# RAMPS2.net
KiCad netlist of a schematic drawn in EAGLE
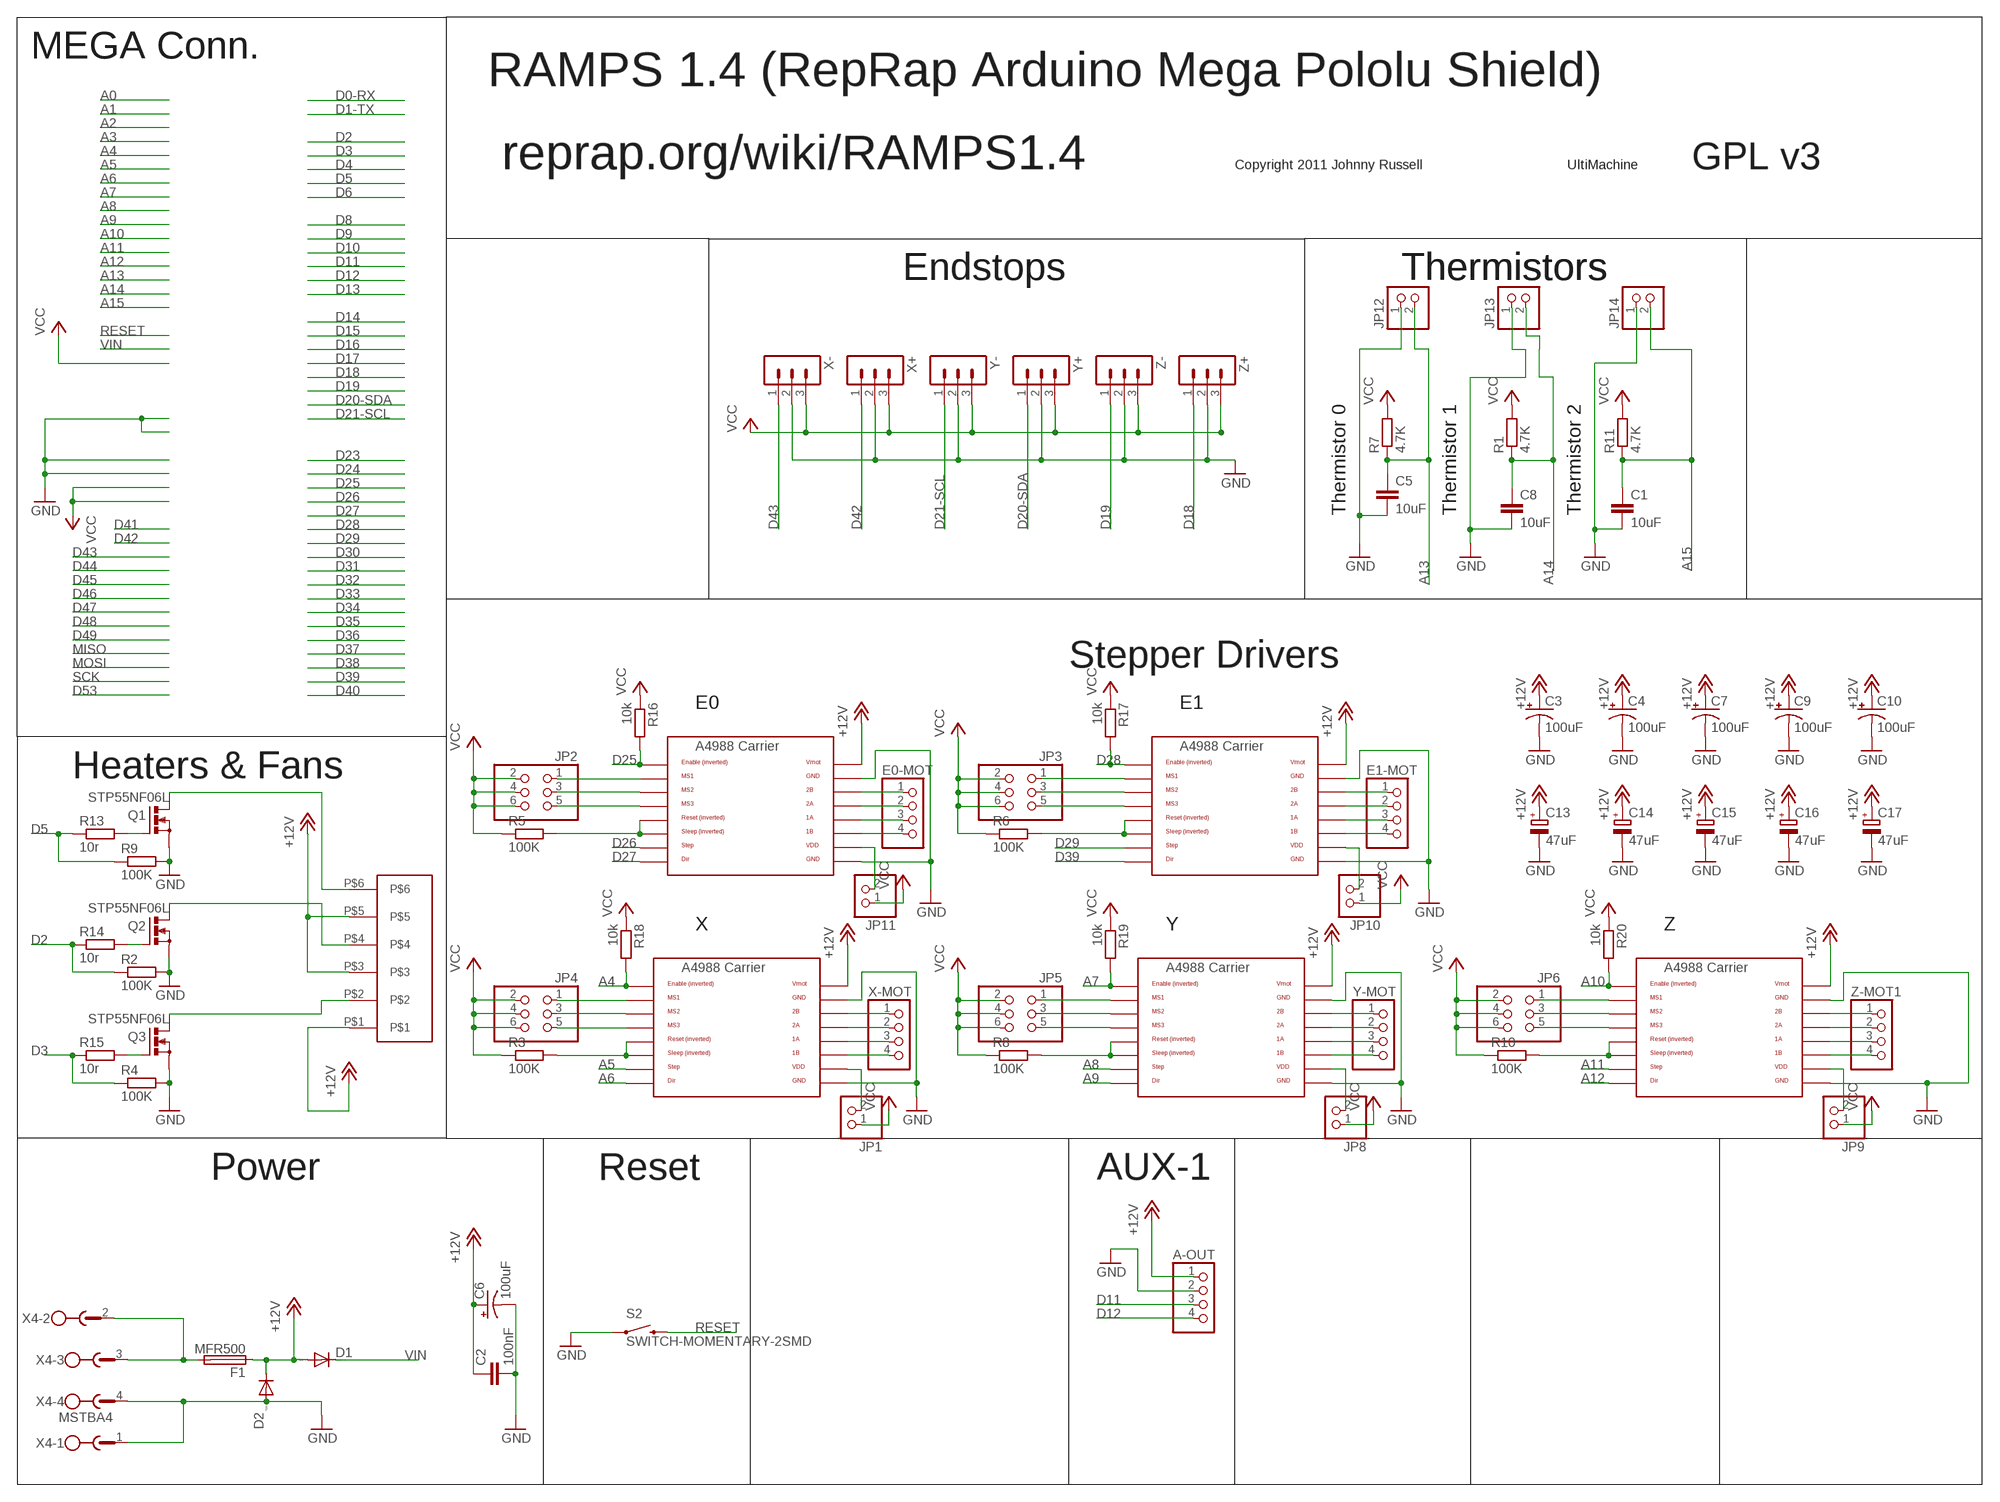
[diagram p0: schematic, sheet 1, part 1 of 3]
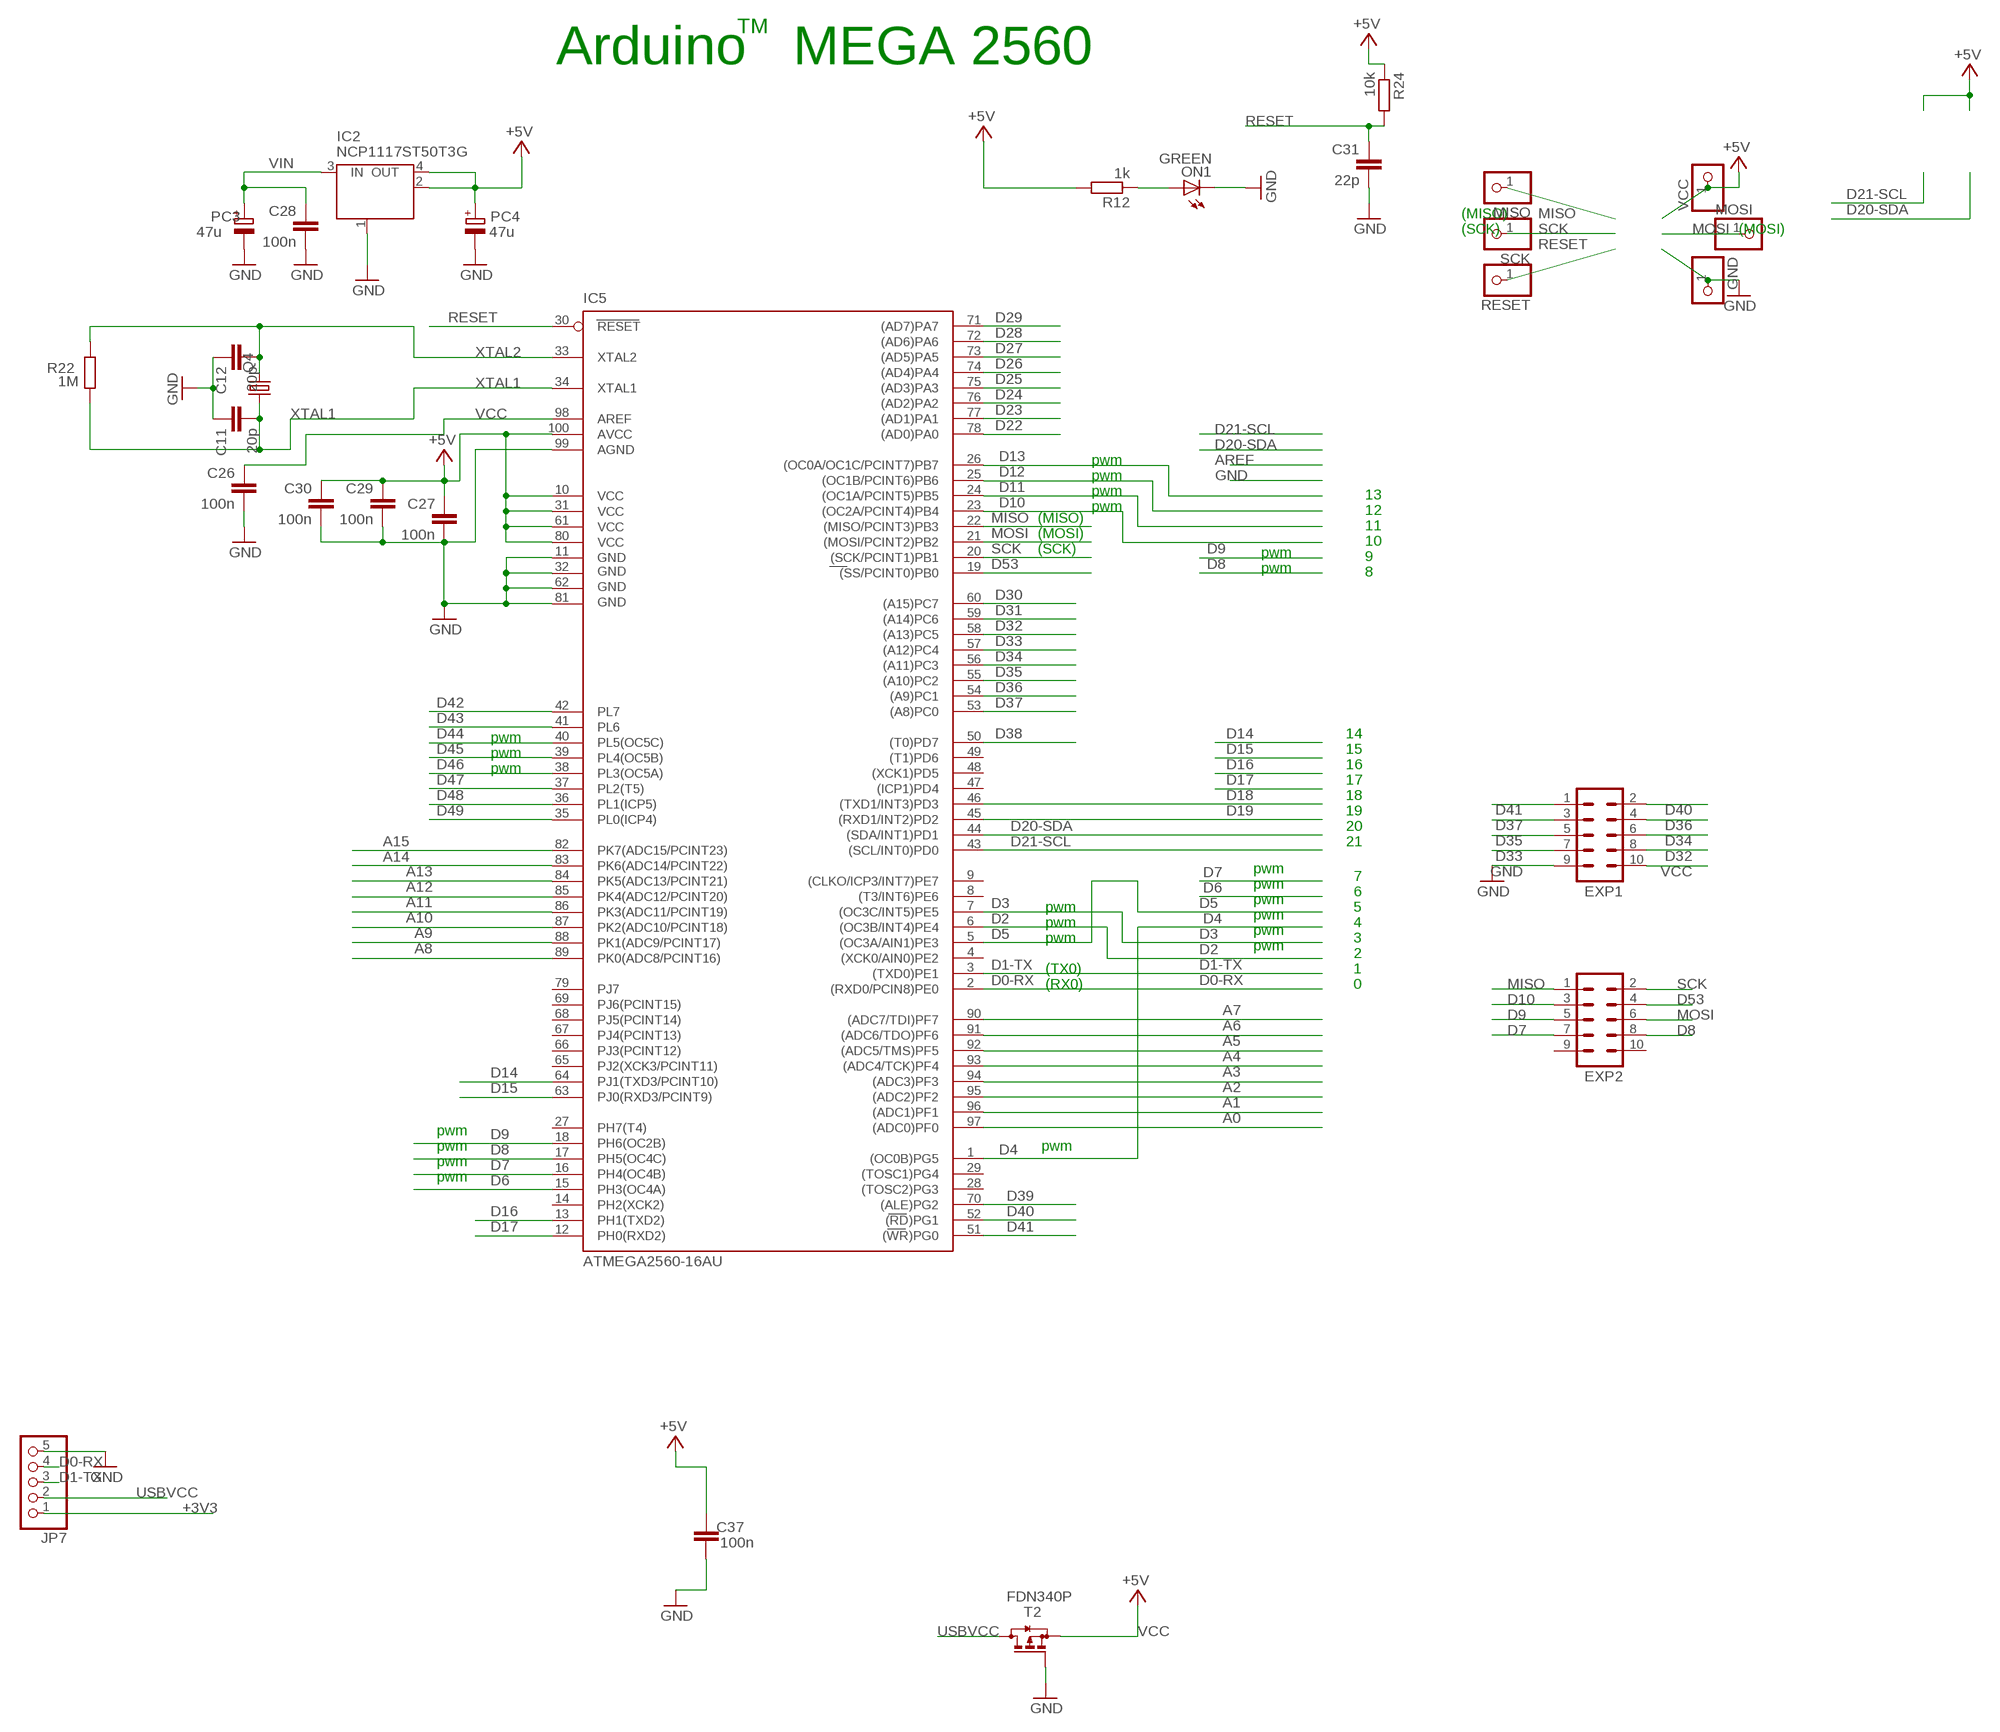
[diagram p1: schematic, sheet 1, part 2 of 3]
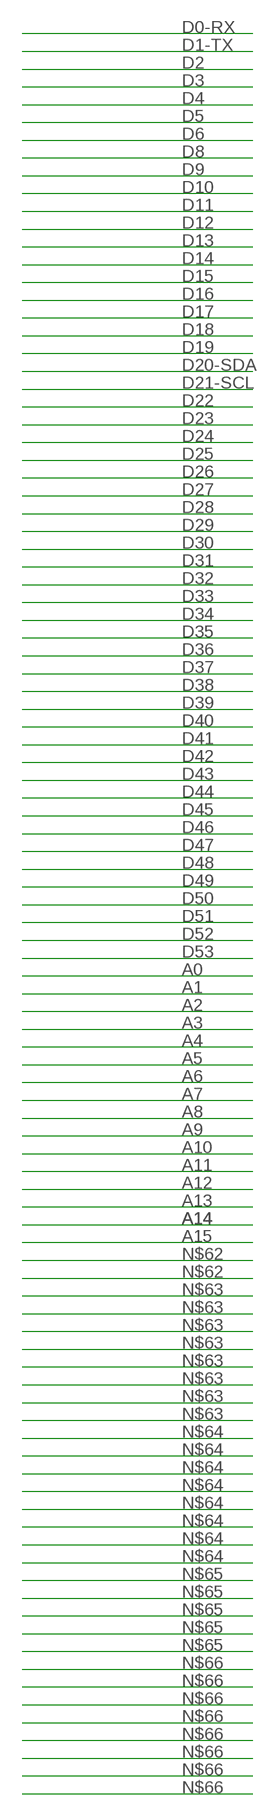
[diagram p2: schematic, sheet 1, part 3 of 3]

(export (version "E")
  (design (tool "Eeschema 10.0.6"))
  (components
    (comp (ref "A-OUT")
      (value "PINHD-1X4")
      (footprint "eagle-import:1X04")
      (libsource (lib "eagle-import") (part "PINHD-1X4"))
    )
    (comp (ref "C1")
      (value "10uF")
      (footprint "eagle-import:C0805")
      (libsource (lib "eagle-import") (part "C-EUC0805"))
    )
    (comp (ref "C2")
      (value "100nF")
      (footprint "eagle-import:C0805")
      (libsource (lib "eagle-import") (part "C-EUC0805"))
    )
    (comp (ref "C3")
      (value "100uF")
      (footprint "eagle-import:153CLV-0605")
      (libsource (lib "eagle-import") (part "CPOL-US153CLV-0605"))
    )
    (comp (ref "C4")
      (value "100uF")
      (footprint "eagle-import:153CLV-0605")
      (libsource (lib "eagle-import") (part "CPOL-US153CLV-0605"))
    )
    (comp (ref "C5")
      (value "10uF")
      (footprint "eagle-import:C0805")
      (libsource (lib "eagle-import") (part "C-EUC0805"))
    )
    (comp (ref "C6")
      (value "100uF")
      (footprint "eagle-import:153CLV-0605")
      (libsource (lib "eagle-import") (part "CPOL-US153CLV-0605"))
    )
    (comp (ref "C7")
      (value "100uF")
      (footprint "eagle-import:153CLV-0605")
      (libsource (lib "eagle-import") (part "CPOL-US153CLV-0605"))
    )
    (comp (ref "C8")
      (value "10uF")
      (footprint "eagle-import:C0805")
      (libsource (lib "eagle-import") (part "C-EUC0805"))
    )
    (comp (ref "C9")
      (value "100uF")
      (footprint "eagle-import:153CLV-0605")
      (libsource (lib "eagle-import") (part "CPOL-US153CLV-0605"))
    )
    (comp (ref "C10")
      (value "100uF")
      (footprint "eagle-import:153CLV-0605")
      (libsource (lib "eagle-import") (part "CPOL-US153CLV-0605"))
    )
    (comp (ref "C11")
      (value "20p")
      (footprint "eagle-import:C0805")
      (libsource (lib "eagle-import") (part "C-EUC0805"))
    )
    (comp (ref "C12")
      (value "20p")
      (footprint "eagle-import:C0805")
      (libsource (lib "eagle-import") (part "C-EUC0805"))
    )
    (comp (ref "C13")
      (value "47uF")
      (footprint "eagle-import:SMC_E")
      (libsource (lib "eagle-import") (part "CPOL-EUSMCE"))
    )
    (comp (ref "C14")
      (value "47uF")
      (footprint "eagle-import:SMC_E")
      (libsource (lib "eagle-import") (part "CPOL-EUSMCE"))
    )
    (comp (ref "C15")
      (value "47uF")
      (footprint "eagle-import:SMC_E")
      (libsource (lib "eagle-import") (part "CPOL-EUSMCE"))
    )
    (comp (ref "C16")
      (value "47uF")
      (footprint "eagle-import:SMC_E")
      (libsource (lib "eagle-import") (part "CPOL-EUSMCE"))
    )
    (comp (ref "C17")
      (value "47uF")
      (footprint "eagle-import:SMC_E")
      (libsource (lib "eagle-import") (part "CPOL-EUSMCE"))
    )
    (comp (ref "C26")
      (value "100n")
      (footprint "eagle-import:C0805")
      (libsource (lib "eagle-import") (part "C-EUC0805"))
    )
    (comp (ref "C27")
      (value "100n")
      (footprint "eagle-import:C0805")
      (libsource (lib "eagle-import") (part "C-EUC0805"))
    )
    (comp (ref "C28")
      (value "100n")
      (footprint "eagle-import:C0603")
      (libsource (lib "eagle-import") (part "C-EUC0603"))
    )
    (comp (ref "C29")
      (value "100n")
      (footprint "eagle-import:C0805")
      (libsource (lib "eagle-import") (part "C-EUC0805"))
    )
    (comp (ref "C30")
      (value "100n")
      (footprint "eagle-import:C0805")
      (libsource (lib "eagle-import") (part "C-EUC0805"))
    )
    (comp (ref "C31")
      (value "22p")
      (footprint "eagle-import:C0805")
      (libsource (lib "eagle-import") (part "C-EUC0805"))
    )
    (comp (ref "C37")
      (value "100n")
      (footprint "eagle-import:C0805")
      (libsource (lib "eagle-import") (part "C-EUC0805"))
    )
    (comp (ref "D1")
      (value "DIODE-DO-214AC")
      (footprint "eagle-import:DO-214AC")
      (libsource (lib "eagle-import") (part "DIODE-DO-214AC"))
    )
    (comp (ref "D2")
      (value "DIODE-DO-214AC")
      (footprint "eagle-import:DO-214AC")
      (libsource (lib "eagle-import") (part "DIODE-DO-214AC"))
    )
    (comp (ref "E0-MOT")
      (value "PINHD-1X4")
      (footprint "eagle-import:1X04")
      (libsource (lib "eagle-import") (part "PINHD-1X4"))
    )
    (comp (ref "E1-MOT")
      (value "PINHD-1X4")
      (footprint "eagle-import:1X04")
      (libsource (lib "eagle-import") (part "PINHD-1X4"))
    )
    (comp (ref "EXP1")
      (value "ML10")
      (footprint "eagle-import:ML10")
      (libsource (lib "eagle-import") (part "ML10"))
    )
    (comp (ref "EXP2")
      (value "ML10")
      (footprint "eagle-import:ML10")
      (libsource (lib "eagle-import") (part "ML10"))
    )
    (comp (ref "F1")
      (value "MFR500")
      (footprint "eagle-import:MFR500")
      (libsource (lib "eagle-import") (part "PTCFUSE"))
    )
    (comp (ref "GND")
      (value "PINHD-1X1")
      (footprint "eagle-import:1X01")
      (libsource (lib "eagle-import") (part "PINHD-1X1"))
    )
    (comp (ref "IC2")
      (value "NCP1117ST50T3G")
      (footprint "eagle-import:SOT223")
      (libsource (lib "eagle-import") (part "MC33269ST-3.3T3"))
    )
    (comp (ref "IC5")
      (value "ATMEGA2560-16AU")
      (footprint "eagle-import:TQFP100")
      (libsource (lib "eagle-import") (part "ATMEGA2560AU2560-16"))
    )
    (comp (ref "JP1")
      (value "PINHD-1X2")
      (footprint "eagle-import:1X02")
      (libsource (lib "eagle-import") (part "PINHD-1X2"))
    )
    (comp (ref "JP2")
      (value "PINHD-2X3")
      (footprint "eagle-import:2X03")
      (libsource (lib "eagle-import") (part "PINHD-2X3"))
    )
    (comp (ref "JP3")
      (value "PINHD-2X3")
      (footprint "eagle-import:2X03")
      (libsource (lib "eagle-import") (part "PINHD-2X3"))
    )
    (comp (ref "JP4")
      (value "PINHD-2X3")
      (footprint "eagle-import:2X03")
      (libsource (lib "eagle-import") (part "PINHD-2X3"))
    )
    (comp (ref "JP5")
      (value "PINHD-2X3")
      (footprint "eagle-import:2X03")
      (libsource (lib "eagle-import") (part "PINHD-2X3"))
    )
    (comp (ref "JP6")
      (value "PINHD-2X3")
      (footprint "eagle-import:2X03")
      (libsource (lib "eagle-import") (part "PINHD-2X3"))
    )
    (comp (ref "JP7")
      (value "PINHD-1X5")
      (footprint "eagle-import:1X05")
      (libsource (lib "eagle-import") (part "PINHD-1X5"))
    )
    (comp (ref "JP8")
      (value "PINHD-1X2")
      (footprint "eagle-import:1X02")
      (libsource (lib "eagle-import") (part "PINHD-1X2"))
    )
    (comp (ref "JP9")
      (value "PINHD-1X2")
      (footprint "eagle-import:1X02")
      (libsource (lib "eagle-import") (part "PINHD-1X2"))
    )
    (comp (ref "JP10")
      (value "PINHD-1X2")
      (footprint "eagle-import:1X02")
      (libsource (lib "eagle-import") (part "PINHD-1X2"))
    )
    (comp (ref "JP11")
      (value "PINHD-1X2")
      (footprint "eagle-import:1X02")
      (libsource (lib "eagle-import") (part "PINHD-1X2"))
    )
    (comp (ref "JP12")
      (value "PINHD-1X2")
      (footprint "eagle-import:1X02")
      (libsource (lib "eagle-import") (part "PINHD-1X2"))
    )
    (comp (ref "JP13")
      (value "PINHD-1X2")
      (footprint "eagle-import:1X02")
      (libsource (lib "eagle-import") (part "PINHD-1X2"))
    )
    (comp (ref "JP14")
      (value "PINHD-1X2")
      (footprint "eagle-import:1X02")
      (libsource (lib "eagle-import") (part "PINHD-1X2"))
    )
    (comp (ref "MISO")
      (value "PINHD-1X1")
      (footprint "eagle-import:1X01")
      (libsource (lib "eagle-import") (part "PINHD-1X1"))
    )
    (comp (ref "MOSI")
      (value "PINHD-1X1")
      (footprint "eagle-import:1X01")
      (libsource (lib "eagle-import") (part "PINHD-1X1"))
    )
    (comp (ref "ON1")
      (value "GREEN")
      (footprint "eagle-import:LED1206")
      (libsource (lib "eagle-import") (part "LED1206"))
    )
    (comp (ref "PC3")
      (value "47u")
      (footprint "eagle-import:PANASONIC_D")
      (libsource (lib "eagle-import") (part "CPOL-EUD"))
    )
    (comp (ref "PC4")
      (value "47u")
      (footprint "eagle-import:PANASONIC_D")
      (libsource (lib "eagle-import") (part "CPOL-EUD"))
    )
    (comp (ref "Q1")
      (value "STP55NF06L")
      (footprint "eagle-import:TO220BV")
      (libsource (lib "eagle-import") (part "IRF512"))
    )
    (comp (ref "Q2")
      (value "STP55NF06L")
      (footprint "eagle-import:TO220BV")
      (libsource (lib "eagle-import") (part "IRF512"))
    )
    (comp (ref "Q3")
      (value "STP55NF06L")
      (footprint "eagle-import:TO220BV")
      (libsource (lib "eagle-import") (part "IRF512"))
    )
    (comp (ref "Q4")
      (value "CRYSTALHC49S")
      (footprint "eagle-import:HC49_S")
      (libsource (lib "eagle-import") (part "CRYSTALHC49S"))
    )
    (comp (ref "R1")
      (value "4.7K")
      (footprint "eagle-import:R0805")
      (libsource (lib "eagle-import") (part "R-EU_R0805"))
    )
    (comp (ref "R2")
      (value "100K")
      (footprint "eagle-import:R0805")
      (libsource (lib "eagle-import") (part "R-EU_R0805"))
    )
    (comp (ref "R3")
      (value "100K")
      (footprint "eagle-import:R0805")
      (libsource (lib "eagle-import") (part "R-EU_R0805"))
    )
    (comp (ref "R4")
      (value "100K")
      (footprint "eagle-import:R0805")
      (libsource (lib "eagle-import") (part "R-EU_R0805"))
    )
    (comp (ref "R5")
      (value "100K")
      (footprint "eagle-import:R0805")
      (libsource (lib "eagle-import") (part "R-EU_R0805"))
    )
    (comp (ref "R6")
      (value "100K")
      (footprint "eagle-import:R0805")
      (libsource (lib "eagle-import") (part "R-EU_R0805"))
    )
    (comp (ref "R7")
      (value "4.7K")
      (footprint "eagle-import:R0805")
      (libsource (lib "eagle-import") (part "R-EU_R0805"))
    )
    (comp (ref "R8")
      (value "100K")
      (footprint "eagle-import:R0805")
      (libsource (lib "eagle-import") (part "R-EU_R0805"))
    )
    (comp (ref "R9")
      (value "100K")
      (footprint "eagle-import:R0805")
      (libsource (lib "eagle-import") (part "R-EU_R0805"))
    )
    (comp (ref "R10")
      (value "100K")
      (footprint "eagle-import:R0805")
      (libsource (lib "eagle-import") (part "R-EU_R0805"))
    )
    (comp (ref "R11")
      (value "4.7K")
      (footprint "eagle-import:R0805")
      (libsource (lib "eagle-import") (part "R-EU_R0805"))
    )
    (comp (ref "R12")
      (value "1k")
      (footprint "eagle-import:R0805")
      (libsource (lib "eagle-import") (part "R-EU_R0805"))
    )
    (comp (ref "R13")
      (value "10r")
      (footprint "eagle-import:R0805")
      (libsource (lib "eagle-import") (part "R-EU_R0805"))
    )
    (comp (ref "R14")
      (value "10r")
      (footprint "eagle-import:R0805")
      (libsource (lib "eagle-import") (part "R-EU_R0805"))
    )
    (comp (ref "R15")
      (value "10r")
      (footprint "eagle-import:R0805")
      (libsource (lib "eagle-import") (part "R-EU_R0805"))
    )
    (comp (ref "R16")
      (value "10k")
      (footprint "eagle-import:R0805")
      (libsource (lib "eagle-import") (part "R-EU_R0805"))
    )
    (comp (ref "R17")
      (value "10k")
      (footprint "eagle-import:R0805")
      (libsource (lib "eagle-import") (part "R-EU_R0805"))
    )
    (comp (ref "R18")
      (value "10k")
      (footprint "eagle-import:R0805")
      (libsource (lib "eagle-import") (part "R-EU_R0805"))
    )
    (comp (ref "R19")
      (value "10k")
      (footprint "eagle-import:R0805")
      (libsource (lib "eagle-import") (part "R-EU_R0805"))
    )
    (comp (ref "R20")
      (value "10k")
      (footprint "eagle-import:R0805")
      (libsource (lib "eagle-import") (part "R-EU_R0805"))
    )
    (comp (ref "R22")
      (value "1M")
      (footprint "eagle-import:R0805")
      (libsource (lib "eagle-import") (part "R-EU_R0805"))
    )
    (comp (ref "R24")
      (value "10k")
      (footprint "eagle-import:R0805")
      (libsource (lib "eagle-import") (part "R-EU_R0805"))
    )
    (comp (ref "RESET")
      (value "PINHD-1X1")
      (footprint "eagle-import:1X01")
      (libsource (lib "eagle-import") (part "PINHD-1X1"))
    )
    (comp (ref "S2")
      (value "SWITCH-MOMENTARY-2SMD")
      (footprint "eagle-import:TACTILE-SWITCH-SMD")
      (libsource (lib "eagle-import") (part "SWITCH-MOMENTARY-2SMD"))
    )
    (comp (ref "SCK")
      (value "PINHD-1X1")
      (footprint "eagle-import:1X01")
      (libsource (lib "eagle-import") (part "PINHD-1X1"))
    )
    (comp (ref "T2")
      (value "FDN340P")
      (footprint "eagle-import:SOT23")
      (libsource (lib "eagle-import") (part "BSS84"))
    )
    (comp (ref "U$2")
      (value "282837-6")
      (footprint "eagle-import:282837-6")
      (libsource (lib "eagle-import") (part "282837-6"))
    )
    (comp (ref "U$4")
      (value "A4988BREAKOUT")
      (footprint "eagle-import:A4988BREAKOUT")
      (libsource (lib "eagle-import") (part "A4988BREAKOUT"))
    )
    (comp (ref "U$5")
      (value "A4988BREAKOUT")
      (footprint "eagle-import:A4988BREAKOUT")
      (libsource (lib "eagle-import") (part "A4988BREAKOUT"))
    )
    (comp (ref "U$6")
      (value "A4988BREAKOUT")
      (footprint "eagle-import:A4988BREAKOUT")
      (libsource (lib "eagle-import") (part "A4988BREAKOUT"))
    )
    (comp (ref "U$7")
      (value "A4988BREAKOUT")
      (footprint "eagle-import:A4988BREAKOUT")
      (libsource (lib "eagle-import") (part "A4988BREAKOUT"))
    )
    (comp (ref "U$8")
      (value "A4988BREAKOUT")
      (footprint "eagle-import:A4988BREAKOUT")
      (libsource (lib "eagle-import") (part "A4988BREAKOUT"))
    )
    (comp (ref "VCC")
      (value "PINHD-1X1")
      (footprint "eagle-import:1X01")
      (libsource (lib "eagle-import") (part "PINHD-1X1"))
    )
    (comp (ref "X+")
      (value "3PIN-HEADER")
      (footprint "eagle-import:3PIN-HEADER")
      (libsource (lib "eagle-import") (part "3PIN-HEADER"))
    )
    (comp (ref "X-")
      (value "3PIN-HEADER")
      (footprint "eagle-import:3PIN-HEADER")
      (libsource (lib "eagle-import") (part "3PIN-HEADER"))
    )
    (comp (ref "X-MOT")
      (value "PINHD-1X4")
      (footprint "eagle-import:1X04")
      (libsource (lib "eagle-import") (part "PINHD-1X4"))
    )
    (comp (ref "X4")
      (value "MSTBA4")
      (footprint "eagle-import:MSTBA4")
      (fields (field (name "MF") "FARNELL") (field (name "MPN") "1757268"))
      (libsource (lib "eagle-import") (part "MSTBA4"))
    )
    (comp (ref "Y+")
      (value "3PIN-HEADER")
      (footprint "eagle-import:3PIN-HEADER")
      (libsource (lib "eagle-import") (part "3PIN-HEADER"))
    )
    (comp (ref "Y-")
      (value "3PIN-HEADER")
      (footprint "eagle-import:3PIN-HEADER")
      (libsource (lib "eagle-import") (part "3PIN-HEADER"))
    )
    (comp (ref "Y-MOT")
      (value "PINHD-1X4")
      (footprint "eagle-import:1X04")
      (libsource (lib "eagle-import") (part "PINHD-1X4"))
    )
    (comp (ref "Z+")
      (value "3PIN-HEADER")
      (footprint "eagle-import:3PIN-HEADER")
      (libsource (lib "eagle-import") (part "3PIN-HEADER"))
    )
    (comp (ref "Z-")
      (value "3PIN-HEADER")
      (footprint "eagle-import:3PIN-HEADER")
      (libsource (lib "eagle-import") (part "3PIN-HEADER"))
    )
    (comp (ref "Z-MOT1")
      (value "PINHD-1X4")
      (footprint "eagle-import:1X04")
      (libsource (lib "eagle-import") (part "PINHD-1X4"))
    )
  )
  (nets
    (net (code "1") (name "+5V") (class "Default")
      (node (ref "C27") (pin "1") (pinfunction "1_1") (pintype "passive"))
      (node (ref "C29") (pin "1") (pinfunction "1_1") (pintype "passive"))
      (node (ref "C30") (pin "1") (pinfunction "1_1") (pintype "passive"))
      (node (ref "C37") (pin "2") (pinfunction "2_2") (pintype "passive"))
      (node (ref "EXP1") (pin "10") (pinfunction "10_10") (pintype "passive"))
      (node (ref "IC2") (pin "2") (pinfunction "OUT_2") (pintype "passive"))
      (node (ref "IC2") (pin "4") (pinfunction "OUT_4") (pintype "passive"))
      (node (ref "IC5") (pin "10") (pinfunction "VCC_10") (pintype "power_in"))
      (node (ref "IC5") (pin "100") (pinfunction "AVCC_100") (pintype "power_in"))
      (node (ref "IC5") (pin "31") (pinfunction "VCC1_31") (pintype "power_in"))
      (node (ref "IC5") (pin "61") (pinfunction "VCC2_61") (pintype "power_in"))
      (node (ref "IC5") (pin "80") (pinfunction "VCC3_80") (pintype "power_in"))
      (node (ref "JP1") (pin "1") (pinfunction "1_1") (pintype "passive"))
      (node (ref "JP10") (pin "1") (pinfunction "1_1") (pintype "passive"))
      (node (ref "JP11") (pin "1") (pinfunction "1_1") (pintype "passive"))
      (node (ref "JP2") (pin "2") (pinfunction "2_2") (pintype "passive"))
      (node (ref "JP2") (pin "4") (pinfunction "4_4") (pintype "passive"))
      (node (ref "JP2") (pin "6") (pinfunction "6_6") (pintype "passive"))
      (node (ref "JP3") (pin "2") (pinfunction "2_2") (pintype "passive"))
      (node (ref "JP3") (pin "4") (pinfunction "4_4") (pintype "passive"))
      (node (ref "JP3") (pin "6") (pinfunction "6_6") (pintype "passive"))
      (node (ref "JP4") (pin "2") (pinfunction "2_2") (pintype "passive"))
      (node (ref "JP4") (pin "4") (pinfunction "4_4") (pintype "passive"))
      (node (ref "JP4") (pin "6") (pinfunction "6_6") (pintype "passive"))
      (node (ref "JP5") (pin "2") (pinfunction "2_2") (pintype "passive"))
      (node (ref "JP5") (pin "4") (pinfunction "4_4") (pintype "passive"))
      (node (ref "JP5") (pin "6") (pinfunction "6_6") (pintype "passive"))
      (node (ref "JP6") (pin "2") (pinfunction "2_2") (pintype "passive"))
      (node (ref "JP6") (pin "4") (pinfunction "4_4") (pintype "passive"))
      (node (ref "JP6") (pin "6") (pinfunction "6_6") (pintype "passive"))
      (node (ref "JP8") (pin "1") (pinfunction "1_1") (pintype "passive"))
      (node (ref "JP9") (pin "1") (pinfunction "1_1") (pintype "passive"))
      (node (ref "PC4") (pin "+") (pinfunction "+_+") (pintype "passive"))
      (node (ref "R1") (pin "2") (pinfunction "2_2") (pintype "passive"))
      (node (ref "R10") (pin "1") (pinfunction "1_1") (pintype "passive"))
      (node (ref "R11") (pin "2") (pinfunction "2_2") (pintype "passive"))
      (node (ref "R12") (pin "2") (pinfunction "2_2") (pintype "passive"))
      (node (ref "R16") (pin "1") (pinfunction "1_1") (pintype "passive"))
      (node (ref "R17") (pin "1") (pinfunction "1_1") (pintype "passive"))
      (node (ref "R18") (pin "1") (pinfunction "1_1") (pintype "passive"))
      (node (ref "R19") (pin "1") (pinfunction "1_1") (pintype "passive"))
      (node (ref "R20") (pin "1") (pinfunction "1_1") (pintype "passive"))
      (node (ref "R24") (pin "1") (pinfunction "1_1") (pintype "passive"))
      (node (ref "R3") (pin "1") (pinfunction "1_1") (pintype "passive"))
      (node (ref "R5") (pin "1") (pinfunction "1_1") (pintype "passive"))
      (node (ref "R6") (pin "1") (pinfunction "1_1") (pintype "passive"))
      (node (ref "R7") (pin "2") (pinfunction "2_2") (pintype "passive"))
      (node (ref "R8") (pin "1") (pinfunction "1_1") (pintype "passive"))
      (node (ref "T2") (pin "2") (pinfunction "S_2") (pintype "passive"))
      (node (ref "VCC") (pin "1") (pinfunction "1_1") (pintype "passive"))
      (node (ref "X+") (pin "3") (pinfunction "3_3") (pintype "passive"))
      (node (ref "X-") (pin "3") (pinfunction "3_3") (pintype "passive"))
      (node (ref "Y+") (pin "3") (pinfunction "3_3") (pintype "passive"))
      (node (ref "Y-") (pin "3") (pinfunction "3_3") (pintype "passive"))
      (node (ref "Z+") (pin "3") (pinfunction "3_3") (pintype "passive"))
      (node (ref "Z-") (pin "3") (pinfunction "3_3") (pintype "passive"))
    )
    (net (code "2") (name "+12V") (class "Default")
      (node (ref "A-OUT") (pin "1") (pinfunction "1_1") (pintype "passive"))
      (node (ref "C10") (pin "+") (pinfunction "+_+") (pintype "passive"))
      (node (ref "C13") (pin "+") (pinfunction "+_+") (pintype "passive"))
      (node (ref "C14") (pin "+") (pinfunction "+_+") (pintype "passive"))
      (node (ref "C15") (pin "+") (pinfunction "+_+") (pintype "passive"))
      (node (ref "C16") (pin "+") (pinfunction "+_+") (pintype "passive"))
      (node (ref "C17") (pin "+") (pinfunction "+_+") (pintype "passive"))
      (node (ref "C2") (pin "1") (pinfunction "1_1") (pintype "passive"))
      (node (ref "C3") (pin "+") (pinfunction "+_+") (pintype "passive"))
      (node (ref "C4") (pin "+") (pinfunction "+_+") (pintype "passive"))
      (node (ref "C6") (pin "+") (pinfunction "+_+") (pintype "passive"))
      (node (ref "C7") (pin "+") (pinfunction "+_+") (pintype "passive"))
      (node (ref "C9") (pin "+") (pinfunction "+_+") (pintype "passive"))
      (node (ref "D1") (pin "A") (pinfunction "A_A") (pintype "passive"))
      (node (ref "D2") (pin "C") (pinfunction "C_C") (pintype "passive"))
      (node (ref "F1") (pin "1") (pinfunction "1_1") (pintype "passive"))
      (node (ref "U$2") (pin "P$1") (pinfunction "P$1_P$1") (pintype "bidirectional"))
      (node (ref "U$2") (pin "P$3") (pinfunction "P$3_P$3") (pintype "bidirectional"))
      (node (ref "U$2") (pin "P$5") (pinfunction "P$5_P$5") (pintype "bidirectional"))
      (node (ref "U$4") (pin "VMOT") (pinfunction "VMOT_VMOT") (pintype "power_in"))
      (node (ref "U$5") (pin "VMOT") (pinfunction "VMOT_VMOT") (pintype "power_in"))
      (node (ref "U$6") (pin "VMOT") (pinfunction "VMOT_VMOT") (pintype "power_in"))
      (node (ref "U$7") (pin "VMOT") (pinfunction "VMOT_VMOT") (pintype "power_in"))
      (node (ref "U$8") (pin "VMOT") (pinfunction "VMOT_VMOT") (pintype "power_in"))
    )
    (net (code "3") (name "/+3V3") (class "Default")
      (node (ref "JP7") (pin "1") (pinfunction "1_1") (pintype "passive"))
    )
    (net (code "4") (name "/A0") (class "Default")
      (node (ref "IC5") (pin "97") (pinfunction "(ADC0)PF0_97") (pintype "bidirectional"))
    )
    (net (code "5") (name "/A1") (class "Default")
      (node (ref "IC5") (pin "96") (pinfunction "(ADC1)PF1_96") (pintype "bidirectional"))
    )
    (net (code "6") (name "/A2") (class "Default")
      (node (ref "IC5") (pin "95") (pinfunction "(ADC2)PF2_95") (pintype "bidirectional"))
    )
    (net (code "7") (name "/A3") (class "Default")
      (node (ref "IC5") (pin "94") (pinfunction "(ADC3)PF3_94") (pintype "bidirectional"))
    )
    (net (code "8") (name "/A4") (class "Default")
      (node (ref "IC5") (pin "93") (pinfunction "(ADC4/TCK)PF4_93") (pintype "bidirectional"))
      (node (ref "R18") (pin "2") (pinfunction "2_2") (pintype "passive"))
      (node (ref "U$6") (pin "EN") (pinfunction "EN_EN") (pintype "input"))
    )
    (net (code "9") (name "/A5") (class "Default")
      (node (ref "IC5") (pin "92") (pinfunction "(ADC5/TMS)PF5_92") (pintype "bidirectional"))
      (node (ref "U$6") (pin "STEP") (pinfunction "STEP_STEP") (pintype "input"))
    )
    (net (code "10") (name "/A6") (class "Default")
      (node (ref "IC5") (pin "91") (pinfunction "(ADC6/TDO)PF6_91") (pintype "bidirectional"))
      (node (ref "U$6") (pin "DIR") (pinfunction "DIR_DIR") (pintype "input"))
    )
    (net (code "11") (name "/A7") (class "Default")
      (node (ref "IC5") (pin "90") (pinfunction "(ADC7/TDI)PF7_90") (pintype "bidirectional"))
      (node (ref "R19") (pin "2") (pinfunction "2_2") (pintype "passive"))
      (node (ref "U$7") (pin "EN") (pinfunction "EN_EN") (pintype "input"))
    )
    (net (code "12") (name "/A8") (class "Default")
      (node (ref "IC5") (pin "89") (pinfunction "PK0(ADC8/PCINT16)_89") (pintype "bidirectional"))
      (node (ref "U$7") (pin "STEP") (pinfunction "STEP_STEP") (pintype "input"))
    )
    (net (code "13") (name "/A9") (class "Default")
      (node (ref "IC5") (pin "88") (pinfunction "PK1(ADC9/PCINT17)_88") (pintype "bidirectional"))
      (node (ref "U$7") (pin "DIR") (pinfunction "DIR_DIR") (pintype "input"))
    )
    (net (code "14") (name "/A10") (class "Default")
      (node (ref "IC5") (pin "87") (pinfunction "PK2(ADC10/PCINT18)_87") (pintype "bidirectional"))
      (node (ref "R20") (pin "2") (pinfunction "2_2") (pintype "passive"))
      (node (ref "U$8") (pin "EN") (pinfunction "EN_EN") (pintype "input"))
    )
    (net (code "15") (name "/A11") (class "Default")
      (node (ref "IC5") (pin "86") (pinfunction "PK3(ADC11/PCINT19)_86") (pintype "bidirectional"))
      (node (ref "U$8") (pin "STEP") (pinfunction "STEP_STEP") (pintype "input"))
    )
    (net (code "16") (name "/A12") (class "Default")
      (node (ref "IC5") (pin "85") (pinfunction "PK4(ADC12/PCINT20)_85") (pintype "bidirectional"))
      (node (ref "U$8") (pin "DIR") (pinfunction "DIR_DIR") (pintype "input"))
    )
    (net (code "17") (name "/A13") (class "Default")
      (node (ref "C5") (pin "1") (pinfunction "1_1") (pintype "passive"))
      (node (ref "IC5") (pin "84") (pinfunction "PK5(ADC13/PCINT21)_84") (pintype "bidirectional"))
      (node (ref "JP12") (pin "2") (pinfunction "2_2") (pintype "passive"))
      (node (ref "R7") (pin "1") (pinfunction "1_1") (pintype "passive"))
    )
    (net (code "18") (name "/A14") (class "Default")
      (node (ref "C8") (pin "1") (pinfunction "1_1") (pintype "passive"))
      (node (ref "IC5") (pin "83") (pinfunction "PK6(ADC14/PCINT22)_83") (pintype "bidirectional"))
      (node (ref "JP13") (pin "2") (pinfunction "2_2") (pintype "passive"))
      (node (ref "R1") (pin "1") (pinfunction "1_1") (pintype "passive"))
    )
    (net (code "19") (name "/A15") (class "Default")
      (node (ref "C1") (pin "1") (pinfunction "1_1") (pintype "passive"))
      (node (ref "IC5") (pin "82") (pinfunction "PK7(ADC15/PCINT23)_82") (pintype "bidirectional"))
      (node (ref "JP14") (pin "2") (pinfunction "2_2") (pintype "passive"))
      (node (ref "R11") (pin "1") (pinfunction "1_1") (pintype "passive"))
    )
    (net (code "21") (name "/D0-RX") (class "Default")
      (node (ref "IC5") (pin "2") (pinfunction "(RXD0/PCIN8)PE0_2") (pintype "bidirectional"))
      (node (ref "JP7") (pin "4") (pinfunction "4_4") (pintype "passive"))
    )
    (net (code "22") (name "/D1-TX") (class "Default")
      (node (ref "IC5") (pin "3") (pinfunction "(TXD0)PE1_3") (pintype "bidirectional"))
      (node (ref "JP7") (pin "3") (pinfunction "3_3") (pintype "passive"))
    )
    (net (code "23") (name "/D2") (class "Default")
      (node (ref "IC5") (pin "6") (pinfunction "(OC3B/INT4)PE4_6") (pintype "bidirectional"))
      (node (ref "R14") (pin "1") (pinfunction "1_1") (pintype "passive"))
      (node (ref "R2") (pin "1") (pinfunction "1_1") (pintype "passive"))
    )
    (net (code "24") (name "/D3") (class "Default")
      (node (ref "IC5") (pin "7") (pinfunction "(OC3C/INT5)PE5_7") (pintype "bidirectional"))
      (node (ref "R15") (pin "1") (pinfunction "1_1") (pintype "passive"))
      (node (ref "R4") (pin "1") (pinfunction "1_1") (pintype "passive"))
    )
    (net (code "25") (name "/D4") (class "Default")
      (node (ref "IC5") (pin "1") (pinfunction "(OC0B)PG5_1") (pintype "bidirectional"))
    )
    (net (code "26") (name "/D5") (class "Default")
      (node (ref "IC5") (pin "5") (pinfunction "(OC3A/AIN1)PE3_5") (pintype "bidirectional"))
      (node (ref "R13") (pin "1") (pinfunction "1_1") (pintype "passive"))
      (node (ref "R9") (pin "1") (pinfunction "1_1") (pintype "passive"))
    )
    (net (code "27") (name "/D6") (class "Default")
      (node (ref "IC5") (pin "15") (pinfunction "PH3(OC4A)_15") (pintype "bidirectional"))
    )
    (net (code "28") (name "/D7") (class "Default")
      (node (ref "EXP2") (pin "7") (pinfunction "7_7") (pintype "passive"))
      (node (ref "IC5") (pin "16") (pinfunction "PH4(OC4B)_16") (pintype "bidirectional"))
    )
    (net (code "29") (name "/D8") (class "Default")
      (node (ref "EXP2") (pin "8") (pinfunction "8_8") (pintype "passive"))
      (node (ref "IC5") (pin "17") (pinfunction "PH5(OC4C)_17") (pintype "bidirectional"))
    )
    (net (code "30") (name "/D9") (class "Default")
      (node (ref "EXP2") (pin "5") (pinfunction "5_5") (pintype "passive"))
      (node (ref "IC5") (pin "18") (pinfunction "PH6(OC2B)_18") (pintype "bidirectional"))
    )
    (net (code "31") (name "/D10") (class "Default")
      (node (ref "EXP2") (pin "3") (pinfunction "3_3") (pintype "passive"))
      (node (ref "IC5") (pin "23") (pinfunction "(OC2A/PCINT4)PB4_23") (pintype "bidirectional"))
    )
    (net (code "32") (name "/D11") (class "Default")
      (node (ref "A-OUT") (pin "3") (pinfunction "3_3") (pintype "passive"))
      (node (ref "IC5") (pin "24") (pinfunction "(OC1A/PCINT5)PB5_24") (pintype "bidirectional"))
    )
    (net (code "33") (name "/D12") (class "Default")
      (node (ref "A-OUT") (pin "4") (pinfunction "4_4") (pintype "passive"))
      (node (ref "IC5") (pin "25") (pinfunction "(OC1B/PCINT6)PB6_25") (pintype "bidirectional"))
    )
    (net (code "34") (name "/D13") (class "Default")
      (node (ref "IC5") (pin "26") (pinfunction "(OC0A/OC1C/PCINT7)PB7_26") (pintype "bidirectional"))
    )
    (net (code "35") (name "/D14") (class "Default")
      (node (ref "IC5") (pin "64") (pinfunction "PJ1(TXD3/PCINT10)_64") (pintype "bidirectional"))
    )
    (net (code "36") (name "/D15") (class "Default")
      (node (ref "IC5") (pin "63") (pinfunction "PJ0(RXD3/PCINT9)_63") (pintype "bidirectional"))
    )
    (net (code "37") (name "/D16") (class "Default")
      (node (ref "IC5") (pin "13") (pinfunction "PH1(TXD2)_13") (pintype "bidirectional"))
    )
    (net (code "38") (name "/D17") (class "Default")
      (node (ref "IC5") (pin "12") (pinfunction "PH0(RXD2)_12") (pintype "bidirectional"))
    )
    (net (code "39") (name "/D18") (class "Default")
      (node (ref "IC5") (pin "46") (pinfunction "(TXD1/INT3)PD3_46") (pintype "bidirectional"))
      (node (ref "Z+") (pin "1") (pinfunction "1_1") (pintype "passive"))
    )
    (net (code "40") (name "/D19") (class "Default")
      (node (ref "IC5") (pin "45") (pinfunction "(RXD1/INT2)PD2_45") (pintype "bidirectional"))
      (node (ref "Z-") (pin "1") (pinfunction "1_1") (pintype "passive"))
    )
    (net (code "41") (name "/D20-SDA") (class "Default")
      (node (ref "IC5") (pin "44") (pinfunction "(SDA/INT1)PD1_44") (pintype "bidirectional"))
      (node (ref "Y+") (pin "1") (pinfunction "1_1") (pintype "passive"))
    )
    (net (code "42") (name "/D21-SCL") (class "Default")
      (node (ref "IC5") (pin "43") (pinfunction "(SCL/INT0)PD0_43") (pintype "bidirectional"))
      (node (ref "Y-") (pin "1") (pinfunction "1_1") (pintype "passive"))
    )
    (net (code "43") (name "/D22") (class "Default")
      (node (ref "IC5") (pin "78") (pinfunction "(AD0)PA0_78") (pintype "bidirectional"))
    )
    (net (code "44") (name "/D23") (class "Default")
      (node (ref "IC5") (pin "77") (pinfunction "(AD1)PA1_77") (pintype "bidirectional"))
    )
    (net (code "45") (name "/D24") (class "Default")
      (node (ref "IC5") (pin "76") (pinfunction "(AD2)PA2_76") (pintype "bidirectional"))
    )
    (net (code "46") (name "/D25") (class "Default")
      (node (ref "IC5") (pin "75") (pinfunction "(AD3)PA3_75") (pintype "bidirectional"))
      (node (ref "R16") (pin "2") (pinfunction "2_2") (pintype "passive"))
      (node (ref "U$4") (pin "EN") (pinfunction "EN_EN") (pintype "input"))
    )
    (net (code "47") (name "/D26") (class "Default")
      (node (ref "IC5") (pin "74") (pinfunction "(AD4)PA4_74") (pintype "bidirectional"))
      (node (ref "U$4") (pin "STEP") (pinfunction "STEP_STEP") (pintype "input"))
    )
    (net (code "48") (name "/D27") (class "Default")
      (node (ref "IC5") (pin "73") (pinfunction "(AD5)PA5_73") (pintype "bidirectional"))
      (node (ref "U$4") (pin "DIR") (pinfunction "DIR_DIR") (pintype "input"))
    )
    (net (code "49") (name "/D28") (class "Default")
      (node (ref "IC5") (pin "72") (pinfunction "(AD6)PA6_72") (pintype "bidirectional"))
      (node (ref "R17") (pin "2") (pinfunction "2_2") (pintype "passive"))
      (node (ref "U$5") (pin "EN") (pinfunction "EN_EN") (pintype "input"))
    )
    (net (code "50") (name "/D29") (class "Default")
      (node (ref "IC5") (pin "71") (pinfunction "(AD7)PA7_71") (pintype "bidirectional"))
      (node (ref "U$5") (pin "STEP") (pinfunction "STEP_STEP") (pintype "input"))
    )
    (net (code "51") (name "/D30") (class "Default")
      (node (ref "IC5") (pin "60") (pinfunction "(A15)PC7_60") (pintype "bidirectional"))
    )
    (net (code "52") (name "/D31") (class "Default")
      (node (ref "IC5") (pin "59") (pinfunction "(A14)PC6_59") (pintype "bidirectional"))
    )
    (net (code "53") (name "/D32") (class "Default")
      (node (ref "EXP1") (pin "8") (pinfunction "8_8") (pintype "passive"))
      (node (ref "IC5") (pin "58") (pinfunction "(A13)PC5_58") (pintype "bidirectional"))
    )
    (net (code "54") (name "/D33") (class "Default")
      (node (ref "EXP1") (pin "7") (pinfunction "7_7") (pintype "passive"))
      (node (ref "IC5") (pin "57") (pinfunction "(A12)PC4_57") (pintype "bidirectional"))
    )
    (net (code "55") (name "/D34") (class "Default")
      (node (ref "EXP1") (pin "6") (pinfunction "6_6") (pintype "passive"))
      (node (ref "IC5") (pin "56") (pinfunction "(A11)PC3_56") (pintype "bidirectional"))
    )
    (net (code "56") (name "/D35") (class "Default")
      (node (ref "EXP1") (pin "5") (pinfunction "5_5") (pintype "passive"))
      (node (ref "IC5") (pin "55") (pinfunction "(A10)PC2_55") (pintype "bidirectional"))
    )
    (net (code "57") (name "/D36") (class "Default")
      (node (ref "EXP1") (pin "4") (pinfunction "4_4") (pintype "passive"))
      (node (ref "IC5") (pin "54") (pinfunction "(A9)PC1_54") (pintype "bidirectional"))
    )
    (net (code "58") (name "/D37") (class "Default")
      (node (ref "EXP1") (pin "3") (pinfunction "3_3") (pintype "passive"))
      (node (ref "IC5") (pin "53") (pinfunction "(A8)PC0_53") (pintype "bidirectional"))
    )
    (net (code "59") (name "/D38") (class "Default")
      (node (ref "IC5") (pin "50") (pinfunction "(T0)PD7_50") (pintype "bidirectional"))
    )
    (net (code "60") (name "/D39") (class "Default")
      (node (ref "IC5") (pin "70") (pinfunction "(ALE)PG2_70") (pintype "bidirectional"))
      (node (ref "U$5") (pin "DIR") (pinfunction "DIR_DIR") (pintype "input"))
    )
    (net (code "61") (name "/D40") (class "Default")
      (node (ref "EXP1") (pin "2") (pinfunction "2_2") (pintype "passive"))
      (node (ref "IC5") (pin "52") (pinfunction "(RD)PG1_52") (pintype "bidirectional"))
    )
    (net (code "62") (name "/D41") (class "Default")
      (node (ref "EXP1") (pin "1") (pinfunction "1_1") (pintype "passive"))
      (node (ref "IC5") (pin "51") (pinfunction "(WR)PG0_51") (pintype "bidirectional"))
    )
    (net (code "63") (name "/D42") (class "Default")
      (node (ref "IC5") (pin "42") (pinfunction "PL7_42") (pintype "bidirectional"))
      (node (ref "X+") (pin "1") (pinfunction "1_1") (pintype "passive"))
    )
    (net (code "64") (name "/D43") (class "Default")
      (node (ref "IC5") (pin "41") (pinfunction "PL6_41") (pintype "bidirectional"))
      (node (ref "X-") (pin "1") (pinfunction "1_1") (pintype "passive"))
    )
    (net (code "65") (name "/D44") (class "Default")
      (node (ref "IC5") (pin "40") (pinfunction "PL5(OC5C)_40") (pintype "bidirectional"))
    )
    (net (code "66") (name "/D45") (class "Default")
      (node (ref "IC5") (pin "39") (pinfunction "PL4(OC5B)_39") (pintype "bidirectional"))
    )
    (net (code "67") (name "/D46") (class "Default")
      (node (ref "IC5") (pin "38") (pinfunction "PL3(OC5A)_38") (pintype "bidirectional"))
    )
    (net (code "68") (name "/D47") (class "Default")
      (node (ref "IC5") (pin "37") (pinfunction "PL2(T5)_37") (pintype "bidirectional"))
    )
    (net (code "69") (name "/D48") (class "Default")
      (node (ref "IC5") (pin "36") (pinfunction "PL1(ICP5)_36") (pintype "bidirectional"))
    )
    (net (code "70") (name "/D49") (class "Default")
      (node (ref "IC5") (pin "35") (pinfunction "PL0(ICP4)_35") (pintype "bidirectional"))
    )
    (net (code "74") (name "/D53") (class "Default")
      (node (ref "EXP2") (pin "4") (pinfunction "4_4") (pintype "passive"))
      (node (ref "IC5") (pin "19") (pinfunction "(SS/PCINT0)PB0_19") (pintype "bidirectional"))
    )
    (net (code "75") (name "/MISO") (class "Default")
      (node (ref "EXP2") (pin "1") (pinfunction "1_1") (pintype "passive"))
      (node (ref "IC5") (pin "22") (pinfunction "(MISO/PCINT3)PB3_22") (pintype "bidirectional"))
      (node (ref "MISO") (pin "1") (pinfunction "1_1") (pintype "passive"))
    )
    (net (code "76") (name "/MOSI") (class "Default")
      (node (ref "EXP2") (pin "6") (pinfunction "6_6") (pintype "passive"))
      (node (ref "IC5") (pin "21") (pinfunction "(MOSI/PCINT2)PB2_21") (pintype "bidirectional"))
      (node (ref "MOSI") (pin "1") (pinfunction "1_1") (pintype "passive"))
    )
    (net (code "82") (name "/RESET") (class "Default")
      (node (ref "C31") (pin "1") (pinfunction "1_1") (pintype "passive"))
      (node (ref "IC5") (pin "30") (pinfunction "RESET_30") (pintype "input"))
      (node (ref "R24") (pin "2") (pinfunction "2_2") (pintype "passive"))
      (node (ref "RESET") (pin "1") (pinfunction "1_1") (pintype "passive"))
      (node (ref "S2") (pin "3") (pinfunction "2_3") (pintype "passive"))
    )
    (net (code "83") (name "/SCK") (class "Default")
      (node (ref "EXP2") (pin "2") (pinfunction "2_2") (pintype "passive"))
      (node (ref "IC5") (pin "20") (pinfunction "(SCK/PCINT1)PB1_20") (pintype "bidirectional"))
      (node (ref "SCK") (pin "1") (pinfunction "1_1") (pintype "passive"))
    )
    (net (code "84") (name "/USBVCC") (class "Default")
      (node (ref "JP7") (pin "2") (pinfunction "2_2") (pintype "passive"))
      (node (ref "T2") (pin "3") (pinfunction "D_3") (pintype "passive"))
    )
    (net (code "85") (name "/VIN") (class "Default")
      (node (ref "C28") (pin "1") (pinfunction "1_1") (pintype "passive"))
      (node (ref "D1") (pin "C") (pinfunction "C_C") (pintype "passive"))
      (node (ref "IC2") (pin "3") (pinfunction "IN_3") (pintype "input"))
      (node (ref "PC3") (pin "+") (pinfunction "+_+") (pintype "passive"))
    )
    (net (code "86") (name "/XTAL1") (class "Default")
      (node (ref "C11") (pin "2") (pinfunction "2_2") (pintype "passive"))
      (node (ref "IC5") (pin "34") (pinfunction "XTAL1_34") (pintype "input"))
      (node (ref "Q4") (pin "1") (pinfunction "1_1") (pintype "passive"))
      (node (ref "R22") (pin "1") (pinfunction "1_1") (pintype "passive"))
    )
    (net (code "87") (name "/XTAL2") (class "Default")
      (node (ref "C12") (pin "2") (pinfunction "2_2") (pintype "passive"))
      (node (ref "IC5") (pin "33") (pinfunction "XTAL2_33") (pintype "output"))
      (node (ref "Q4") (pin "2") (pinfunction "2_2") (pintype "passive"))
      (node (ref "R22") (pin "2") (pinfunction "2_2") (pintype "passive"))
    )
    (net (code "88") (name "GND") (class "Default")
      (node (ref "A-OUT") (pin "2") (pinfunction "2_2") (pintype "passive"))
      (node (ref "C1") (pin "2") (pinfunction "2_2") (pintype "passive"))
      (node (ref "C10") (pin "-") (pinfunction "-_-") (pintype "passive"))
      (node (ref "C11") (pin "1") (pinfunction "1_1") (pintype "passive"))
      (node (ref "C12") (pin "1") (pinfunction "1_1") (pintype "passive"))
      (node (ref "C13") (pin "-") (pinfunction "-_-") (pintype "passive"))
      (node (ref "C14") (pin "-") (pinfunction "-_-") (pintype "passive"))
      (node (ref "C15") (pin "-") (pinfunction "-_-") (pintype "passive"))
      (node (ref "C16") (pin "-") (pinfunction "-_-") (pintype "passive"))
      (node (ref "C17") (pin "-") (pinfunction "-_-") (pintype "passive"))
      (node (ref "C2") (pin "2") (pinfunction "2_2") (pintype "passive"))
      (node (ref "C26") (pin "2") (pinfunction "2_2") (pintype "passive"))
      (node (ref "C27") (pin "2") (pinfunction "2_2") (pintype "passive"))
      (node (ref "C28") (pin "2") (pinfunction "2_2") (pintype "passive"))
      (node (ref "C29") (pin "2") (pinfunction "2_2") (pintype "passive"))
      (node (ref "C3") (pin "-") (pinfunction "-_-") (pintype "passive"))
      (node (ref "C30") (pin "2") (pinfunction "2_2") (pintype "passive"))
      (node (ref "C31") (pin "2") (pinfunction "2_2") (pintype "passive"))
      (node (ref "C37") (pin "1") (pinfunction "1_1") (pintype "passive"))
      (node (ref "C4") (pin "-") (pinfunction "-_-") (pintype "passive"))
      (node (ref "C5") (pin "2") (pinfunction "2_2") (pintype "passive"))
      (node (ref "C6") (pin "-") (pinfunction "-_-") (pintype "passive"))
      (node (ref "C7") (pin "-") (pinfunction "-_-") (pintype "passive"))
      (node (ref "C8") (pin "2") (pinfunction "2_2") (pintype "passive"))
      (node (ref "C9") (pin "-") (pinfunction "-_-") (pintype "passive"))
      (node (ref "D2") (pin "A") (pinfunction "A_A") (pintype "passive"))
      (node (ref "EXP1") (pin "9") (pinfunction "9_9") (pintype "passive"))
      (node (ref "GND") (pin "1") (pinfunction "1_1") (pintype "passive"))
      (node (ref "IC2") (pin "1") (pinfunction "GND/ADJ_1") (pintype "input"))
      (node (ref "IC5") (pin "11") (pinfunction "GND_11") (pintype "power_in"))
      (node (ref "IC5") (pin "32") (pinfunction "GND1_32") (pintype "power_in"))
      (node (ref "IC5") (pin "62") (pinfunction "GND2_62") (pintype "power_in"))
      (node (ref "IC5") (pin "81") (pinfunction "GND3_81") (pintype "power_in"))
      (node (ref "IC5") (pin "99") (pinfunction "AGND_99") (pintype "power_in"))
      (node (ref "JP12") (pin "1") (pinfunction "1_1") (pintype "passive"))
      (node (ref "JP13") (pin "1") (pinfunction "1_1") (pintype "passive"))
      (node (ref "JP14") (pin "1") (pinfunction "1_1") (pintype "passive"))
      (node (ref "JP7") (pin "5") (pinfunction "5_5") (pintype "passive"))
      (node (ref "ON1") (pin "C") (pinfunction "C_C") (pintype "passive"))
      (node (ref "PC3") (pin "-") (pinfunction "-_-") (pintype "passive"))
      (node (ref "PC4") (pin "-") (pinfunction "-_-") (pintype "passive"))
      (node (ref "Q1") (pin "S") (pinfunction "S_S") (pintype "passive"))
      (node (ref "Q2") (pin "S") (pinfunction "S_S") (pintype "passive"))
      (node (ref "Q3") (pin "S") (pinfunction "S_S") (pintype "passive"))
      (node (ref "R2") (pin "2") (pinfunction "2_2") (pintype "passive"))
      (node (ref "R4") (pin "2") (pinfunction "2_2") (pintype "passive"))
      (node (ref "R9") (pin "2") (pinfunction "2_2") (pintype "passive"))
      (node (ref "S2") (pin "1") (pinfunction "1_1") (pintype "passive"))
      (node (ref "T2") (pin "1") (pinfunction "G_1") (pintype "passive"))
      (node (ref "U$4") (pin "GND") (pinfunction "GND_GND") (pintype "power_in"))
      (node (ref "U$4") (pin "GND@0") (pinfunction "GND_GND@0") (pintype "power_in"))
      (node (ref "U$5") (pin "GND") (pinfunction "GND_GND") (pintype "power_in"))
      (node (ref "U$5") (pin "GND@0") (pinfunction "GND_GND@0") (pintype "power_in"))
      (node (ref "U$6") (pin "GND") (pinfunction "GND_GND") (pintype "power_in"))
      (node (ref "U$6") (pin "GND@0") (pinfunction "GND_GND@0") (pintype "power_in"))
      (node (ref "U$7") (pin "GND") (pinfunction "GND_GND") (pintype "power_in"))
      (node (ref "U$7") (pin "GND@0") (pinfunction "GND_GND@0") (pintype "power_in"))
      (node (ref "U$8") (pin "GND") (pinfunction "GND_GND") (pintype "power_in"))
      (node (ref "U$8") (pin "GND@0") (pinfunction "GND_GND@0") (pintype "power_in"))
      (node (ref "X+") (pin "2") (pinfunction "2_2") (pintype "passive"))
      (node (ref "X-") (pin "2") (pinfunction "2_2") (pintype "passive"))
      (node (ref "X4") (pin "1") (pinfunction "1_1") (pintype "passive"))
      (node (ref "X4") (pin "4") (pinfunction "1_4") (pintype "passive"))
      (node (ref "Y+") (pin "2") (pinfunction "2_2") (pintype "passive"))
      (node (ref "Y-") (pin "2") (pinfunction "2_2") (pintype "passive"))
      (node (ref "Z+") (pin "2") (pinfunction "2_2") (pintype "passive"))
      (node (ref "Z-") (pin "2") (pinfunction "2_2") (pintype "passive"))
    )
    (net (code "89") (name "Net-(E0-MOT-Pad1)") (class "Default")
      (node (ref "E0-MOT") (pin "1") (pinfunction "1_1") (pintype "passive"))
      (node (ref "U$4") (pin "2B") (pinfunction "2B_2B") (pintype "output"))
    )
    (net (code "90") (name "Net-(E0-MOT-Pad2)") (class "Default")
      (node (ref "E0-MOT") (pin "2") (pinfunction "2_2") (pintype "passive"))
      (node (ref "U$4") (pin "2A") (pinfunction "2A_2A") (pintype "output"))
    )
    (net (code "91") (name "Net-(E0-MOT-Pad3)") (class "Default")
      (node (ref "E0-MOT") (pin "3") (pinfunction "3_3") (pintype "passive"))
      (node (ref "U$4") (pin "1A") (pinfunction "1A_1A") (pintype "output"))
    )
    (net (code "92") (name "Net-(E0-MOT-Pad4)") (class "Default")
      (node (ref "E0-MOT") (pin "4") (pinfunction "4_4") (pintype "passive"))
      (node (ref "U$4") (pin "1B") (pinfunction "1B_1B") (pintype "output"))
    )
    (net (code "93") (name "Net-(E1-MOT-Pad1)") (class "Default")
      (node (ref "E1-MOT") (pin "1") (pinfunction "1_1") (pintype "passive"))
      (node (ref "U$5") (pin "2B") (pinfunction "2B_2B") (pintype "output"))
    )
    (net (code "94") (name "Net-(E1-MOT-Pad2)") (class "Default")
      (node (ref "E1-MOT") (pin "2") (pinfunction "2_2") (pintype "passive"))
      (node (ref "U$5") (pin "2A") (pinfunction "2A_2A") (pintype "output"))
    )
    (net (code "95") (name "Net-(E1-MOT-Pad3)") (class "Default")
      (node (ref "E1-MOT") (pin "3") (pinfunction "3_3") (pintype "passive"))
      (node (ref "U$5") (pin "1A") (pinfunction "1A_1A") (pintype "output"))
    )
    (net (code "96") (name "Net-(E1-MOT-Pad4)") (class "Default")
      (node (ref "E1-MOT") (pin "4") (pinfunction "4_4") (pintype "passive"))
      (node (ref "U$5") (pin "1B") (pinfunction "1B_1B") (pintype "output"))
    )
    (net (code "97") (name "Net-(IC5-AREF)") (class "Default")
      (node (ref "C26") (pin "1") (pinfunction "1_1") (pintype "passive"))
      (node (ref "IC5") (pin "98") (pinfunction "AREF_98") (pintype "bidirectional"))
    )
    (net (code "98") (name "Net-(JP1-Pad2)") (class "Default")
      (node (ref "JP1") (pin "2") (pinfunction "2_2") (pintype "passive"))
      (node (ref "U$6") (pin "VDD") (pinfunction "VDD_VDD") (pintype "power_in"))
    )
    (net (code "99") (name "Net-(JP2-Pad1)") (class "Default")
      (node (ref "JP2") (pin "1") (pinfunction "1_1") (pintype "passive"))
      (node (ref "U$4") (pin "MS1") (pinfunction "MS1_MS1") (pintype "input"))
    )
    (net (code "100") (name "Net-(JP2-Pad3)") (class "Default")
      (node (ref "JP2") (pin "3") (pinfunction "3_3") (pintype "passive"))
      (node (ref "U$4") (pin "MS2") (pinfunction "MS2_MS2") (pintype "input"))
    )
    (net (code "101") (name "Net-(JP2-Pad5)") (class "Default")
      (node (ref "JP2") (pin "5") (pinfunction "5_5") (pintype "passive"))
      (node (ref "U$4") (pin "MS3") (pinfunction "MS3_MS3") (pintype "input"))
    )
    (net (code "102") (name "Net-(JP3-Pad1)") (class "Default")
      (node (ref "JP3") (pin "1") (pinfunction "1_1") (pintype "passive"))
      (node (ref "U$5") (pin "MS1") (pinfunction "MS1_MS1") (pintype "input"))
    )
    (net (code "103") (name "Net-(JP3-Pad3)") (class "Default")
      (node (ref "JP3") (pin "3") (pinfunction "3_3") (pintype "passive"))
      (node (ref "U$5") (pin "MS2") (pinfunction "MS2_MS2") (pintype "input"))
    )
    (net (code "104") (name "Net-(JP3-Pad5)") (class "Default")
      (node (ref "JP3") (pin "5") (pinfunction "5_5") (pintype "passive"))
      (node (ref "U$5") (pin "MS3") (pinfunction "MS3_MS3") (pintype "input"))
    )
    (net (code "105") (name "Net-(JP4-Pad1)") (class "Default")
      (node (ref "JP4") (pin "1") (pinfunction "1_1") (pintype "passive"))
      (node (ref "U$6") (pin "MS1") (pinfunction "MS1_MS1") (pintype "input"))
    )
    (net (code "106") (name "Net-(JP4-Pad3)") (class "Default")
      (node (ref "JP4") (pin "3") (pinfunction "3_3") (pintype "passive"))
      (node (ref "U$6") (pin "MS2") (pinfunction "MS2_MS2") (pintype "input"))
    )
    (net (code "107") (name "Net-(JP4-Pad5)") (class "Default")
      (node (ref "JP4") (pin "5") (pinfunction "5_5") (pintype "passive"))
      (node (ref "U$6") (pin "MS3") (pinfunction "MS3_MS3") (pintype "input"))
    )
    (net (code "108") (name "Net-(JP5-Pad1)") (class "Default")
      (node (ref "JP5") (pin "1") (pinfunction "1_1") (pintype "passive"))
      (node (ref "U$7") (pin "MS1") (pinfunction "MS1_MS1") (pintype "input"))
    )
    (net (code "109") (name "Net-(JP5-Pad3)") (class "Default")
      (node (ref "JP5") (pin "3") (pinfunction "3_3") (pintype "passive"))
      (node (ref "U$7") (pin "MS2") (pinfunction "MS2_MS2") (pintype "input"))
    )
    (net (code "110") (name "Net-(JP5-Pad5)") (class "Default")
      (node (ref "JP5") (pin "5") (pinfunction "5_5") (pintype "passive"))
      (node (ref "U$7") (pin "MS3") (pinfunction "MS3_MS3") (pintype "input"))
    )
    (net (code "111") (name "Net-(JP6-Pad1)") (class "Default")
      (node (ref "JP6") (pin "1") (pinfunction "1_1") (pintype "passive"))
      (node (ref "U$8") (pin "MS1") (pinfunction "MS1_MS1") (pintype "input"))
    )
    (net (code "112") (name "Net-(JP6-Pad3)") (class "Default")
      (node (ref "JP6") (pin "3") (pinfunction "3_3") (pintype "passive"))
      (node (ref "U$8") (pin "MS2") (pinfunction "MS2_MS2") (pintype "input"))
    )
    (net (code "113") (name "Net-(JP6-Pad5)") (class "Default")
      (node (ref "JP6") (pin "5") (pinfunction "5_5") (pintype "passive"))
      (node (ref "U$8") (pin "MS3") (pinfunction "MS3_MS3") (pintype "input"))
    )
    (net (code "114") (name "Net-(JP8-Pad2)") (class "Default")
      (node (ref "JP8") (pin "2") (pinfunction "2_2") (pintype "passive"))
      (node (ref "U$7") (pin "VDD") (pinfunction "VDD_VDD") (pintype "power_in"))
    )
    (net (code "115") (name "Net-(JP9-Pad2)") (class "Default")
      (node (ref "JP9") (pin "2") (pinfunction "2_2") (pintype "passive"))
      (node (ref "U$8") (pin "VDD") (pinfunction "VDD_VDD") (pintype "power_in"))
    )
    (net (code "116") (name "Net-(JP10-Pad2)") (class "Default")
      (node (ref "JP10") (pin "2") (pinfunction "2_2") (pintype "passive"))
      (node (ref "U$5") (pin "VDD") (pinfunction "VDD_VDD") (pintype "power_in"))
    )
    (net (code "117") (name "Net-(JP11-Pad2)") (class "Default")
      (node (ref "JP11") (pin "2") (pinfunction "2_2") (pintype "passive"))
      (node (ref "U$4") (pin "VDD") (pinfunction "VDD_VDD") (pintype "power_in"))
    )
    (net (code "118") (name "Net-(ON1-PadA)") (class "Default")
      (node (ref "ON1") (pin "A") (pinfunction "A_A") (pintype "passive"))
      (node (ref "R12") (pin "1") (pinfunction "1_1") (pintype "passive"))
    )
    (net (code "119") (name "Net-(Q1-PadD)") (class "Default")
      (node (ref "Q1") (pin "D") (pinfunction "D_D") (pintype "passive"))
      (node (ref "U$2") (pin "P$6") (pinfunction "P$6_P$6") (pintype "bidirectional"))
    )
    (net (code "120") (name "Net-(Q1-PadG)") (class "Default")
      (node (ref "Q1") (pin "G") (pinfunction "G_G") (pintype "passive"))
      (node (ref "R13") (pin "2") (pinfunction "2_2") (pintype "passive"))
    )
    (net (code "121") (name "Net-(Q2-PadD)") (class "Default")
      (node (ref "Q2") (pin "D") (pinfunction "D_D") (pintype "passive"))
      (node (ref "U$2") (pin "P$4") (pinfunction "P$4_P$4") (pintype "bidirectional"))
    )
    (net (code "122") (name "Net-(Q2-PadG)") (class "Default")
      (node (ref "Q2") (pin "G") (pinfunction "G_G") (pintype "passive"))
      (node (ref "R14") (pin "2") (pinfunction "2_2") (pintype "passive"))
    )
    (net (code "123") (name "Net-(Q3-PadD)") (class "Default")
      (node (ref "Q3") (pin "D") (pinfunction "D_D") (pintype "passive"))
      (node (ref "U$2") (pin "P$2") (pinfunction "P$2_P$2") (pintype "bidirectional"))
    )
    (net (code "124") (name "Net-(Q3-PadG)") (class "Default")
      (node (ref "Q3") (pin "G") (pinfunction "G_G") (pintype "passive"))
      (node (ref "R15") (pin "2") (pinfunction "2_2") (pintype "passive"))
    )
    (net (code "125") (name "Net-(U$4-SLEEP)") (class "Default")
      (node (ref "R5") (pin "2") (pinfunction "2_2") (pintype "passive"))
      (node (ref "U$4") (pin "RST") (pinfunction "RST_RST") (pintype "input"))
      (node (ref "U$4") (pin "SLP") (pinfunction "SLEEP_SLP") (pintype "input"))
    )
    (net (code "126") (name "Net-(U$5-SLEEP)") (class "Default")
      (node (ref "R6") (pin "2") (pinfunction "2_2") (pintype "passive"))
      (node (ref "U$5") (pin "RST") (pinfunction "RST_RST") (pintype "input"))
      (node (ref "U$5") (pin "SLP") (pinfunction "SLEEP_SLP") (pintype "input"))
    )
    (net (code "127") (name "Net-(U$6-Pad1A)") (class "Default")
      (node (ref "U$6") (pin "1A") (pinfunction "1A_1A") (pintype "output"))
      (node (ref "X-MOT") (pin "3") (pinfunction "3_3") (pintype "passive"))
    )
    (net (code "128") (name "Net-(U$6-Pad1B)") (class "Default")
      (node (ref "U$6") (pin "1B") (pinfunction "1B_1B") (pintype "output"))
      (node (ref "X-MOT") (pin "4") (pinfunction "4_4") (pintype "passive"))
    )
    (net (code "129") (name "Net-(U$6-Pad2A)") (class "Default")
      (node (ref "U$6") (pin "2A") (pinfunction "2A_2A") (pintype "output"))
      (node (ref "X-MOT") (pin "2") (pinfunction "2_2") (pintype "passive"))
    )
    (net (code "130") (name "Net-(U$6-Pad2B)") (class "Default")
      (node (ref "U$6") (pin "2B") (pinfunction "2B_2B") (pintype "output"))
      (node (ref "X-MOT") (pin "1") (pinfunction "1_1") (pintype "passive"))
    )
    (net (code "131") (name "Net-(U$6-SLEEP)") (class "Default")
      (node (ref "R3") (pin "2") (pinfunction "2_2") (pintype "passive"))
      (node (ref "U$6") (pin "RST") (pinfunction "RST_RST") (pintype "input"))
      (node (ref "U$6") (pin "SLP") (pinfunction "SLEEP_SLP") (pintype "input"))
    )
    (net (code "132") (name "Net-(U$7-Pad1A)") (class "Default")
      (node (ref "U$7") (pin "1A") (pinfunction "1A_1A") (pintype "output"))
      (node (ref "Y-MOT") (pin "3") (pinfunction "3_3") (pintype "passive"))
    )
    (net (code "133") (name "Net-(U$7-Pad1B)") (class "Default")
      (node (ref "U$7") (pin "1B") (pinfunction "1B_1B") (pintype "output"))
      (node (ref "Y-MOT") (pin "4") (pinfunction "4_4") (pintype "passive"))
    )
    (net (code "134") (name "Net-(U$7-Pad2A)") (class "Default")
      (node (ref "U$7") (pin "2A") (pinfunction "2A_2A") (pintype "output"))
      (node (ref "Y-MOT") (pin "2") (pinfunction "2_2") (pintype "passive"))
    )
    (net (code "135") (name "Net-(U$7-Pad2B)") (class "Default")
      (node (ref "U$7") (pin "2B") (pinfunction "2B_2B") (pintype "output"))
      (node (ref "Y-MOT") (pin "1") (pinfunction "1_1") (pintype "passive"))
    )
    (net (code "136") (name "Net-(U$7-SLEEP)") (class "Default")
      (node (ref "R8") (pin "2") (pinfunction "2_2") (pintype "passive"))
      (node (ref "U$7") (pin "RST") (pinfunction "RST_RST") (pintype "input"))
      (node (ref "U$7") (pin "SLP") (pinfunction "SLEEP_SLP") (pintype "input"))
    )
    (net (code "137") (name "Net-(U$8-Pad1A)") (class "Default")
      (node (ref "U$8") (pin "1A") (pinfunction "1A_1A") (pintype "output"))
      (node (ref "Z-MOT1") (pin "3") (pinfunction "3_3") (pintype "passive"))
    )
    (net (code "138") (name "Net-(U$8-Pad1B)") (class "Default")
      (node (ref "U$8") (pin "1B") (pinfunction "1B_1B") (pintype "output"))
      (node (ref "Z-MOT1") (pin "4") (pinfunction "4_4") (pintype "passive"))
    )
    (net (code "139") (name "Net-(U$8-Pad2A)") (class "Default")
      (node (ref "U$8") (pin "2A") (pinfunction "2A_2A") (pintype "output"))
      (node (ref "Z-MOT1") (pin "2") (pinfunction "2_2") (pintype "passive"))
    )
    (net (code "140") (name "Net-(U$8-Pad2B)") (class "Default")
      (node (ref "U$8") (pin "2B") (pinfunction "2B_2B") (pintype "output"))
      (node (ref "Z-MOT1") (pin "1") (pinfunction "1_1") (pintype "passive"))
    )
    (net (code "141") (name "Net-(U$8-SLEEP)") (class "Default")
      (node (ref "R10") (pin "2") (pinfunction "2_2") (pintype "passive"))
      (node (ref "U$8") (pin "RST") (pinfunction "RST_RST") (pintype "input"))
      (node (ref "U$8") (pin "SLP") (pinfunction "SLEEP_SLP") (pintype "input"))
    )
    (net (code "142") (name "Net-(X4B-1)") (class "Default")
      (node (ref "F1") (pin "2") (pinfunction "2_2") (pintype "passive"))
      (node (ref "X4") (pin "2") (pinfunction "1_2") (pintype "passive"))
      (node (ref "X4") (pin "3") (pinfunction "1_3") (pintype "passive"))
    )
    (net (code "143") (name "unconnected-(EXP2-Pad9)") (class "Default")
      (node (ref "EXP2") (pin "9") (pinfunction "9_9") (pintype "passive"))
    )
    (net (code "144") (name "unconnected-(EXP2-Pad10)") (class "Default")
      (node (ref "EXP2") (pin "10") (pinfunction "10_10") (pintype "passive"))
    )
    (net (code "145") (name "unconnected-(IC5-(CLKO{slash}ICP3{slash}INT7)PE7-Pad9)") (class "Default")
      (node (ref "IC5") (pin "9") (pinfunction "(CLKO/ICP3/INT7)PE7_9") (pintype "bidirectional"))
    )
    (net (code "146") (name "unconnected-(IC5-(ICP1)PD4-Pad47)") (class "Default")
      (node (ref "IC5") (pin "47") (pinfunction "(ICP1)PD4_47") (pintype "bidirectional"))
    )
    (net (code "147") (name "unconnected-(IC5-(T1)PD6-Pad49)") (class "Default")
      (node (ref "IC5") (pin "49") (pinfunction "(T1)PD6_49") (pintype "bidirectional"))
    )
    (net (code "148") (name "unconnected-(IC5-(T3{slash}INT6)PE6-Pad8)") (class "Default")
      (node (ref "IC5") (pin "8") (pinfunction "(T3/INT6)PE6_8") (pintype "bidirectional"))
    )
    (net (code "149") (name "unconnected-(IC5-(TOSC1)PG4-Pad29)") (class "Default")
      (node (ref "IC5") (pin "29") (pinfunction "(TOSC1)PG4_29") (pintype "bidirectional"))
    )
    (net (code "150") (name "unconnected-(IC5-(TOSC2)PG3-Pad28)") (class "Default")
      (node (ref "IC5") (pin "28") (pinfunction "(TOSC2)PG3_28") (pintype "bidirectional"))
    )
    (net (code "151") (name "unconnected-(IC5-(XCK0{slash}AIN0)PE2-Pad4)") (class "Default")
      (node (ref "IC5") (pin "4") (pinfunction "(XCK0/AIN0)PE2_4") (pintype "bidirectional"))
    )
    (net (code "152") (name "unconnected-(IC5-(XCK1)PD5-Pad48)") (class "Default")
      (node (ref "IC5") (pin "48") (pinfunction "(XCK1)PD5_48") (pintype "bidirectional"))
    )
    (net (code "153") (name "unconnected-(IC5-PH2(XCK2)-Pad14)") (class "Default")
      (node (ref "IC5") (pin "14") (pinfunction "PH2(XCK2)_14") (pintype "bidirectional"))
    )
    (net (code "154") (name "unconnected-(IC5-PH7(T4)-Pad27)") (class "Default")
      (node (ref "IC5") (pin "27") (pinfunction "PH7(T4)_27") (pintype "bidirectional"))
    )
    (net (code "155") (name "unconnected-(IC5-PJ2(XCK3{slash}PCINT11)-Pad65)") (class "Default")
      (node (ref "IC5") (pin "65") (pinfunction "PJ2(XCK3/PCINT11)_65") (pintype "bidirectional"))
    )
    (net (code "156") (name "unconnected-(IC5-PJ3(PCINT12)-Pad66)") (class "Default")
      (node (ref "IC5") (pin "66") (pinfunction "PJ3(PCINT12)_66") (pintype "bidirectional"))
    )
    (net (code "157") (name "unconnected-(IC5-PJ4(PCINT13)-Pad67)") (class "Default")
      (node (ref "IC5") (pin "67") (pinfunction "PJ4(PCINT13)_67") (pintype "bidirectional"))
    )
    (net (code "158") (name "unconnected-(IC5-PJ5(PCINT14)-Pad68)") (class "Default")
      (node (ref "IC5") (pin "68") (pinfunction "PJ5(PCINT14)_68") (pintype "bidirectional"))
    )
    (net (code "159") (name "unconnected-(IC5-PJ6(PCINT15)-Pad69)") (class "Default")
      (node (ref "IC5") (pin "69") (pinfunction "PJ6(PCINT15)_69") (pintype "bidirectional"))
    )
    (net (code "160") (name "unconnected-(IC5-PJ7-Pad79)") (class "Default")
      (node (ref "IC5") (pin "79") (pinfunction "PJ7_79") (pintype "bidirectional"))
    )
  )
)
